# Main.net
KiCad netlist of a schematic drawn in Altium Designer
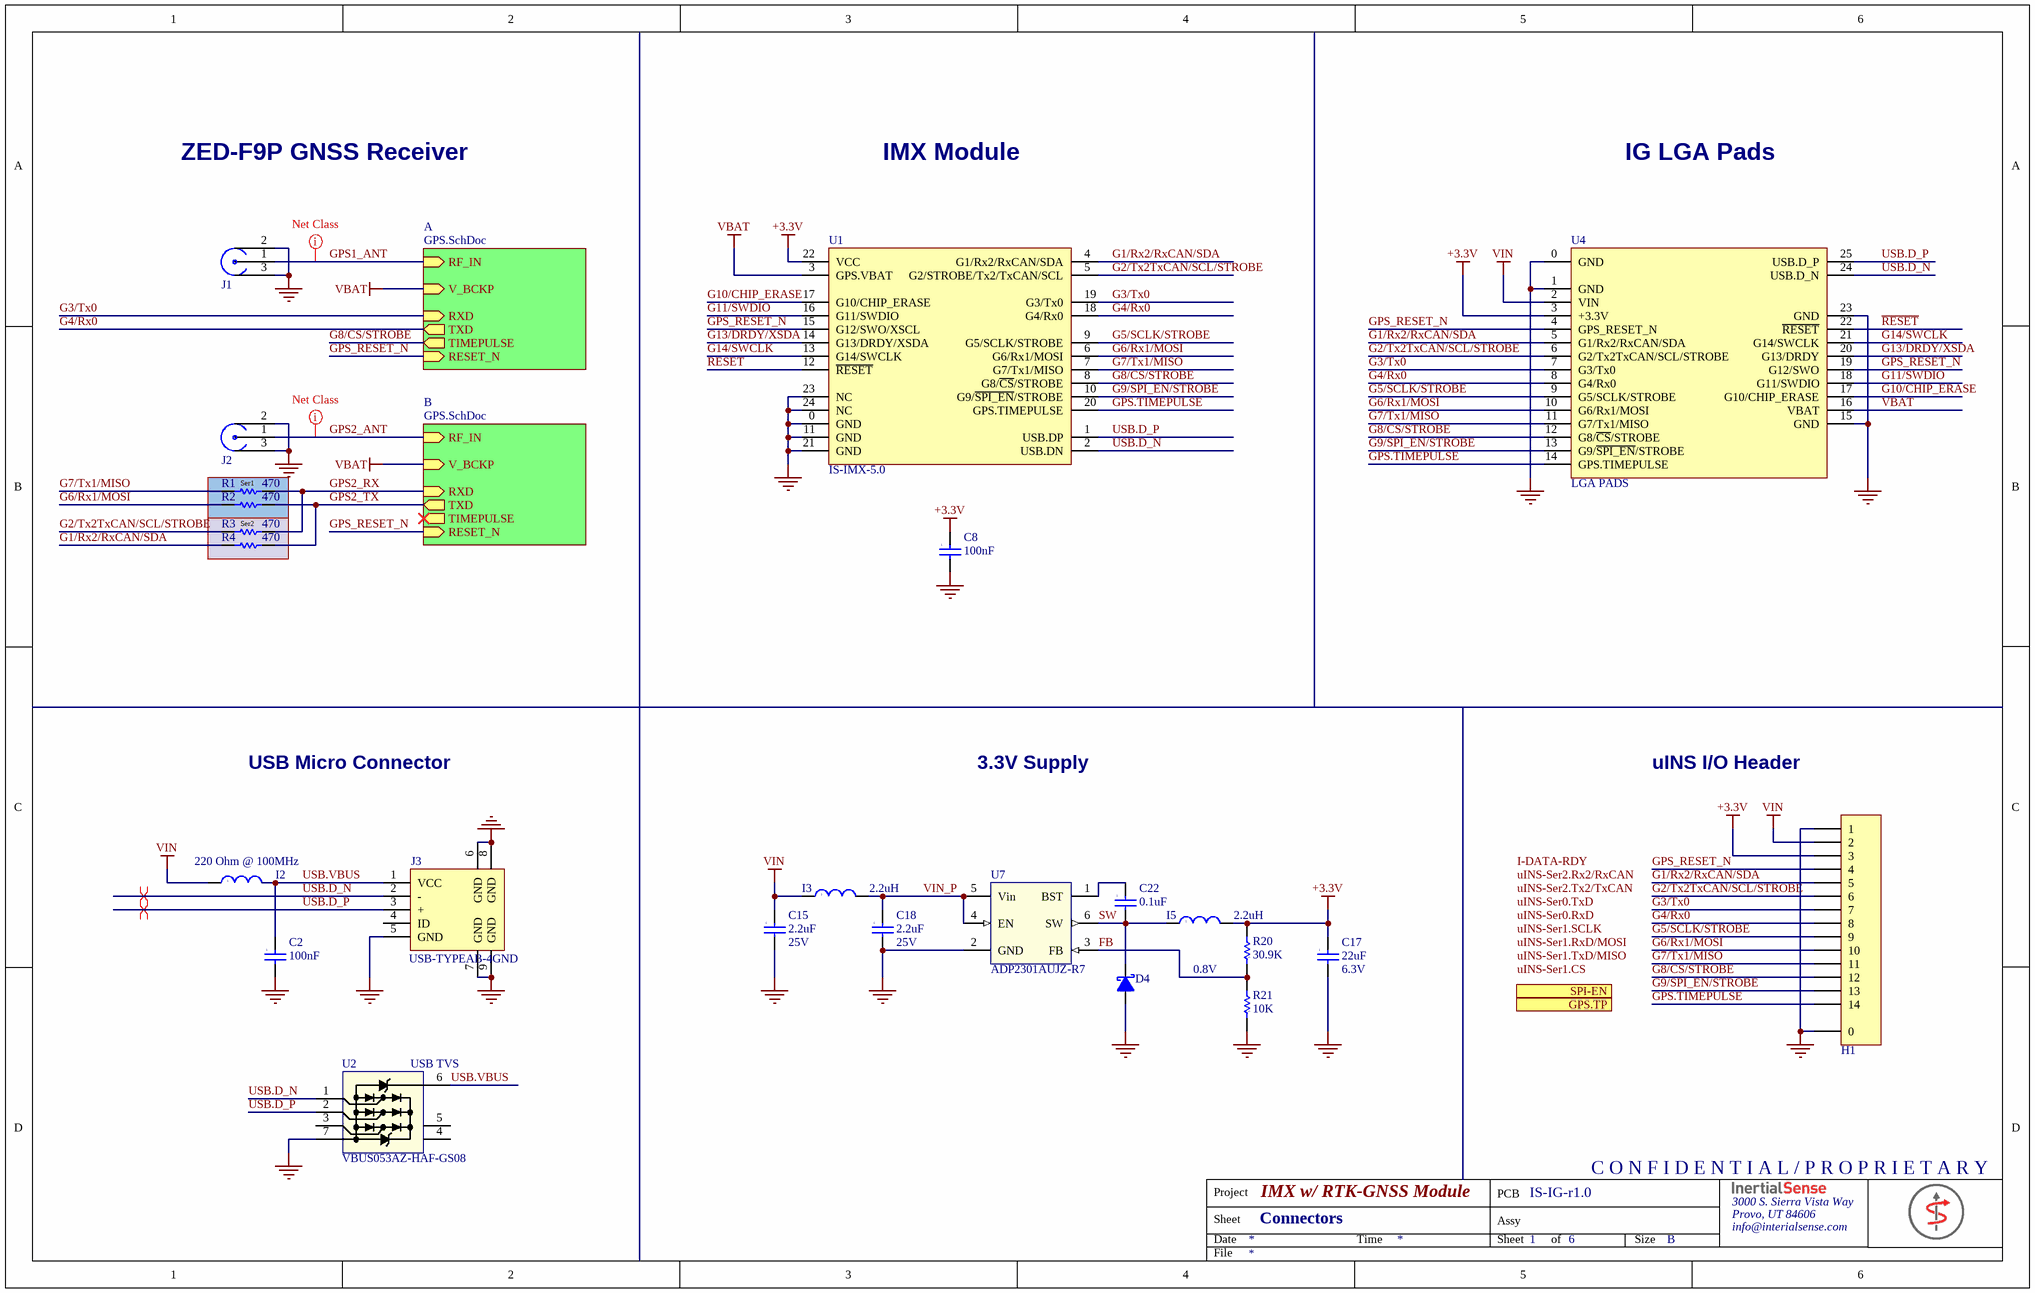
[diagram p0: Main.SchDoc]

(export (version "E")
  (design (tool "Eeschema 10.0.6"))
  (components
    (comp (ref "C2")
      (value "100nF")
      (footprint "0402")
      (description "CAP CER .10UF 50V X7R 10% 0402")
      (fields
        (field (name "MANUFACTURER") "TDK Corporation")
        (field (name "MANUFACTURER PART NUMBER") "C1005X7R1H104K")
        (field (name "PUBLISHER") "Altium Limited")
      )
      (libsource (lib "") (part "Cap_1"))
    )
    (comp (ref "C8")
      (value "100nF")
      (footprint "0402")
      (description "CAP CER .10UF 50V X7R 10% 0402")
      (fields
        (field (name "MANUFACTURER") "TDK Corporation")
        (field (name "MANUFACTURER PART NUMBER") "C1005X7R1H104K")
        (field (name "PUBLISHER") "Altium Limited")
      )
      (libsource (lib "") (part "Cap_1"))
    )
    (comp (ref "C15")
      (value "2.2uF")
      (footprint "0603")
      (description "CAP CER 2.2UF 25V X6S 0603")
      (fields
        (field (name "MANUFACTURER") "Murata")
        (field (name "MANUFACTURER PART NUMBER") "GRT188C81E225KE13D")
        (field (name "VOLTAGE RATING") "25V")
        (field (name "PUBLISHER") "Altium Limited")
      )
      (libsource (lib "General") (part "Cap"))
    )
    (comp (ref "C17")
      (value "22uF")
      (footprint "0603")
      (description "CAP CER 22UF 6.3V X6S 0603")
      (fields
        (field (name "MANUFACTURER") "Murata")
        (field (name "MANUFACTURER PART NUMBER") "GRM188C80J226ME15D")
        (field (name "VOLTAGE RATING") "6.3V")
        (field (name "PUBLISHER") "Altium Limited")
      )
      (libsource (lib "General") (part "Cap"))
    )
    (comp (ref "C18")
      (value "2.2uF")
      (footprint "0603")
      (description "CAP CER 2.2UF 25V X6S 0603")
      (fields
        (field (name "MANUFACTURER") "Murata")
        (field (name "MANUFACTURER PART NUMBER") "GRT188C81E225KE13D")
        (field (name "VOLTAGE RATING") "25V")
        (field (name "PUBLISHER") "Altium Limited")
      )
      (libsource (lib "General") (part "Cap"))
    )
    (comp (ref "C22")
      (value "0.1uF")
      (footprint "0402")
      (description "CAP CER 0.1UF 50V X7R 0402")
      (fields
        (field (name "MANUFACTURER") "TDK")
        (field (name "MANUFACTURER PART NUMBER") "CGA2B3X7R1H104K050BB")
        (field (name "PUBLISHER") "Altium Limited")
      )
      (libsource (lib "General") (part "Cap"))
    )
    (comp (ref "D4")
      (value "Diode - Schottky")
      (footprint "D0603B")
      (description "DIODE SCHOTTKY 30V 2A 0603")
      (fields
        (field (name "MANUFACTURER") "Vishay")
        (field (name "MANUFACTURER PART NUMBER") "VSKY20301608-G4-08")
      )
      (libsource (lib "General") (part "Diode - Schottky"))
    )
    (comp (ref "H1")
      (value "Hdr - 14pin - mount")
      (footprint "SM14B-GHS-TB(LF)(SN)")
      (description "Conn Shrouded Header HDR 14 POS 1.25mm Solder ST Top Entry SMD T/R")
      (fields
        (field (name "MANUFACTURER") "JST")
        (field (name "MANUFACTURER PART NUMBER") "SM14B-GHS-TB(LF)(SN)")
      )
      (libsource (lib "Connectors") (part "Hdr - 14pin - mount"))
    )
    (comp (ref "I2")
      (value "220 Ohm @ 100MHz")
      (footprint "I0603")
      (description "FERRITE CHIP 220 OHM 2500MA 0603")
      (fields
        (field (name "MANUFACTURER") "Murata Electronics North America")
        (field (name "MANUFACTURER PART NUMBER") "BLM18SG221TN1D")
      )
      (libsource (lib "") (part "Inductor_1"))
    )
    (comp (ref "I3")
      (value "2.2uH")
      (footprint "0806")
      (description "FIXED IND 2.2UH 1.2A 110 MOHM")
      (fields
        (field (name "MANUFACTURER") "TDK")
        (field (name "MANUFACTURER PART NUMBER") "MLP2016H2R2MT0S1")
      )
      (libsource (lib "General") (part "Inductor"))
    )
    (comp (ref "I5")
      (value "2.2uH")
      (footprint "0806")
      (description "FIXED IND 2.2UH 1.2A 110 MOHM")
      (fields
        (field (name "MANUFACTURER") "TDK")
        (field (name "MANUFACTURER PART NUMBER") "MLP2016H2R2MT0S1")
      )
      (libsource (lib "General") (part "Inductor"))
    )
    (comp (ref "J1")
      (value "RF - GND x 2")
      (footprint "RF UMC SMD")
      (description "CONN UMC RCPT STR 50 OHM SMD")
      (fields
        (field (name "MANUFACTURER") "Emerson Network Power Connectivity Johnson")
        (field (name "MANUFACTURER PART NUMBER") "128-0711-201")
      )
      (libsource (lib "Connectors") (part "RF - GND x 2"))
    )
    (comp (ref "J2")
      (value "RF - GND x 2")
      (footprint "RF UMC SMD")
      (description "CONN UMC RCPT STR 50 OHM SMD")
      (fields
        (field (name "MANUFACTURER") "Emerson Network Power Connectivity Johnson")
        (field (name "MANUFACTURER PART NUMBER") "128-0711-201")
      )
      (libsource (lib "Connectors") (part "RF - GND x 2"))
    )
    (comp (ref "J3")
      (value "USB-TYPEAB-4GND")
      (footprint "USB Micro AB R/A THR")
      (description "CONN USB AB 4POS")
      (fields
        (field (name "MANUFACTURER") "Amphenol FCI")
        (field (name "MANUFACTURER PART NUMBER") "10118194-0001LF")
      )
      (libsource (lib "Connectors") (part "USB-TYPEAB-4GND"))
    )
    (comp (ref "R1")
      (value "470")
      (footprint "R0402")
      (description "RES 470 OHM 1/16W 1% 0402 SMD")
      (fields
        (field (name "MANUFACTURER") "Vishay Dale")
        (field (name "MANUFACTURER PART NUMBER") "CRCW0402470RFKED")
      )
      (libsource (lib "") (part "Res_1"))
    )
    (comp (ref "R2")
      (value "470")
      (footprint "R0402")
      (description "RES 470 OHM 1/16W 1% 0402 SMD")
      (fields
        (field (name "MANUFACTURER") "Vishay Dale")
        (field (name "MANUFACTURER PART NUMBER") "CRCW0402470RFKED")
      )
      (libsource (lib "") (part "Res_1"))
    )
    (comp (ref "R3")
      (value "470")
      (footprint "R0402")
      (description "RES 470 OHM 1/16W 1% 0402 SMD")
      (fields
        (field (name "MANUFACTURER") "Vishay Dale")
        (field (name "MANUFACTURER PART NUMBER") "CRCW0402470RFKED")
      )
      (libsource (lib "") (part "Res_1"))
    )
    (comp (ref "R4")
      (value "470")
      (footprint "R0402")
      (description "RES 470 OHM 1/16W 1% 0402 SMD")
      (fields
        (field (name "MANUFACTURER") "Vishay Dale")
        (field (name "MANUFACTURER PART NUMBER") "CRCW0402470RFKED")
      )
      (libsource (lib "") (part "Res_1"))
    )
    (comp (ref "R20")
      (value "30.9K")
      (footprint "R0402")
      (description "RES TF 30.9K OHM 1% 1/16W 0402")
      (fields
        (field (name "MANUFACTURER") "Stackpole Electronics Inc")
        (field (name "MANUFACTURER PART NUMBER") "RMCF0402FT30K9")
      )
      (libsource (lib "General") (part "Res"))
    )
    (comp (ref "R21")
      (value "10K")
      (footprint "R0402")
      (description "RES 10.0K OHM 1/16W 1% 0402 SMD")
      (fields
        (field (name "MANUFACTURER") "Yageo")
        (field (name "MANUFACTURER PART NUMBER") "RC0402FR-0710KL")
      )
      (libsource (lib "General") (part "Res"))
    )
    (comp (ref "U1")
      (value "IMX")
      (footprint "IS-IMX-5.0")
      (description "Inertial Sense IMX")
      (fields
        (field (name "MANUFACTURER") "Inertial Sense")
        (field (name "MANUFACTURER PART NUMBER") "IS-IMX-5.0")
      )
      (libsource (lib "IS-IMX-5") (part "IS-IMX-5.0"))
    )
    (comp (ref "U2")
      (value "VBUS053")
      (footprint "QFN50P160X160X60-6N")
      (description "ESD SUPPRESS 5.5V 36W 3-Line USB")
      (fields
        (field (name "MANUFACTURER") "Vishay Semiconductors")
        (field (name "MANUFACTURER PART NUMBER") "VBUS053AZ-HAF-GS08")
      )
      (libsource (lib "ICs") (part "VBUS053"))
    )
    (comp (ref "U4")
      (value "LGA PADS")
      (footprint "IG-1.0_LGA")
      (description "IMX multi-frequency RTK-GNSS Module")
      (libsource (lib "Sensors") (part "IG_1.0_LGA"))
    )
    (comp (ref "U7")
      (value "ADP2301")
      (footprint "MO-178-AB")
      (description "IC BUCK ADJ 1.2A 6TSOT")
      (fields
        (field (name "MANUFACTURER") "Analog Devices Inc")
        (field (name "MANUFACTURER PART NUMBER") "ADP2301AUJZ-R7")
      )
      (libsource (lib "ICs") (part "ADP2301"))
    )
  )
  (nets
    (net (code "1") (name "+3.3V") (class "Default")
      (node (ref "C17") (pin "1") (pinfunction "1_1") (pintype "passive"))
      (node (ref "C8") (pin "1") (pinfunction "1_1") (pintype "passive"))
      (node (ref "H1") (pin "3") (pinfunction "3_3") (pintype "passive"))
      (node (ref "I5") (pin "2") (pinfunction "2_2") (pintype "passive"))
      (node (ref "R20") (pin "2") (pinfunction "2_2") (pintype "passive"))
      (node (ref "U1") (pin "22") (pinfunction "VCC_22") (pintype "power_in"))
      (node (ref "U4") (pin "3") (pinfunction "+3.3V_3") (pintype "passive"))
    )
    (net (code "2") (name "/FB") (class "Default")
      (node (ref "R20") (pin "1") (pinfunction "1_1") (pintype "passive"))
      (node (ref "R21") (pin "2") (pinfunction "2_2") (pintype "passive"))
      (node (ref "U7") (pin "3") (pinfunction "FB_3") (pintype "input"))
    )
    (net (code "3") (name "/G1{slash}Rx2{slash}RxCAN{slash}SDA") (class "Default")
      (node (ref "H1") (pin "5") (pinfunction "5_5") (pintype "passive"))
      (node (ref "R4") (pin "1") (pinfunction "1_1") (pintype "passive"))
      (node (ref "U1") (pin "4") (pinfunction "G1/Rx2/RxCAN/SDA_4") (pintype "passive"))
      (node (ref "U4") (pin "5") (pinfunction "G1/Rx2/RxCAN/SDA_5") (pintype "passive"))
    )
    (net (code "4") (name "/G2{slash}Tx2TxCAN{slash}SCL{slash}STROBE") (class "Default")
      (node (ref "H1") (pin "6") (pinfunction "6_6") (pintype "passive"))
      (node (ref "R3") (pin "1") (pinfunction "1_1") (pintype "passive"))
      (node (ref "U1") (pin "5") (pinfunction "G2/STROBE/Tx2/TxCAN/SCL_5") (pintype "passive"))
      (node (ref "U4") (pin "6") (pinfunction "G2/Tx2TxCAN/SCL/STROBE_6") (pintype "passive"))
    )
    (net (code "5") (name "/G3{slash}Tx0") (class "Default")
      (node (ref "H1") (pin "7") (pinfunction "7_7") (pintype "passive"))
      (node (ref "U1") (pin "19") (pinfunction "G3/Tx0_19") (pintype "passive"))
      (node (ref "U4") (pin "7") (pinfunction "G3/Tx0_7") (pintype "passive"))
    )
    (net (code "6") (name "/G4{slash}Rx0") (class "Default")
      (node (ref "H1") (pin "8") (pinfunction "8_8") (pintype "passive"))
      (node (ref "U1") (pin "18") (pinfunction "G4/Rx0_18") (pintype "passive"))
      (node (ref "U4") (pin "8") (pinfunction "G4/Rx0_8") (pintype "passive"))
    )
    (net (code "7") (name "/G5{slash}SCLK{slash}STROBE") (class "Default")
      (node (ref "H1") (pin "9") (pinfunction "9_9") (pintype "passive"))
      (node (ref "U1") (pin "9") (pinfunction "G5/SCLK/STROBE_9") (pintype "passive"))
      (node (ref "U4") (pin "9") (pinfunction "G5/SCLK/STROBE_9") (pintype "passive"))
    )
    (net (code "8") (name "/G6{slash}Rx1{slash}MOSI") (class "Default")
      (node (ref "H1") (pin "10") (pinfunction "10_10") (pintype "passive"))
      (node (ref "R2") (pin "1") (pinfunction "1_1") (pintype "passive"))
      (node (ref "U1") (pin "6") (pinfunction "G6/Rx1/MOSI_6") (pintype "passive"))
      (node (ref "U4") (pin "10") (pinfunction "G6/Rx1/MOSI_10") (pintype "passive"))
    )
    (net (code "9") (name "/G7{slash}Tx1{slash}MISO") (class "Default")
      (node (ref "H1") (pin "11") (pinfunction "11_11") (pintype "passive"))
      (node (ref "R1") (pin "1") (pinfunction "1_1") (pintype "passive"))
      (node (ref "U1") (pin "7") (pinfunction "G7/Tx1/MISO_7") (pintype "passive"))
      (node (ref "U4") (pin "11") (pinfunction "G7/Tx1/MISO_11") (pintype "passive"))
    )
    (net (code "10") (name "/G8{slash}~{CS}{slash}STROBE") (class "Default")
      (node (ref "H1") (pin "12") (pinfunction "12_12") (pintype "passive"))
      (node (ref "U1") (pin "8") (pinfunction "G8/~{CS}/STROBE_8") (pintype "passive"))
      (node (ref "U4") (pin "12") (pinfunction "G8/~{CS}/STROBE_12") (pintype "passive"))
    )
    (net (code "11") (name "/G9{slash}~{SPI_EN}{slash}STROBE") (class "Default")
      (node (ref "H1") (pin "13") (pinfunction "13_13") (pintype "passive"))
      (node (ref "U1") (pin "10") (pinfunction "G9/~{SPI_EN}/STROBE_10") (pintype "passive"))
      (node (ref "U4") (pin "13") (pinfunction "G9/~{SPI_EN}/STROBE_13") (pintype "passive"))
    )
    (net (code "12") (name "/G10{slash}CHIP_ERASE") (class "Default")
      (node (ref "U1") (pin "17") (pinfunction "G10/CHIP_ERASE_17") (pintype "passive"))
      (node (ref "U4") (pin "17") (pinfunction "G10/CHIP_ERASE_17") (pintype "passive"))
    )
    (net (code "13") (name "/G11{slash}SWDIO") (class "Default")
      (node (ref "U1") (pin "16") (pinfunction "G11/SWDIO_16") (pintype "passive"))
      (node (ref "U4") (pin "18") (pinfunction "G11/SWDIO_18") (pintype "passive"))
    )
    (net (code "14") (name "/G13{slash}DRDY{slash}XSDA") (class "Default")
      (node (ref "U1") (pin "14") (pinfunction "G13/DRDY/XSDA_14") (pintype "passive"))
      (node (ref "U4") (pin "20") (pinfunction "G13/DRDY_20") (pintype "passive"))
    )
    (net (code "15") (name "/G14{slash}SWCLK") (class "Default")
      (node (ref "U1") (pin "13") (pinfunction "G14/SWCLK_13") (pintype "passive"))
      (node (ref "U4") (pin "21") (pinfunction "G14/SWCLK_21") (pintype "passive"))
    )
    (net (code "16") (name "/GPS.TIMEPULSE") (class "Default")
      (node (ref "H1") (pin "14") (pinfunction "14_14") (pintype "passive"))
      (node (ref "U1") (pin "20") (pinfunction "GPS.TIMEPULSE_20") (pintype "passive"))
      (node (ref "U4") (pin "14") (pinfunction "GPS.TIMEPULSE_14") (pintype "passive"))
    )
    (net (code "18") (name "/GPS1_ANT") (class "Default")
      (node (ref "J1") (pin "1") (pinfunction "1_1") (pintype "passive"))
    )
    (net (code "19") (name "/GPS2_ANT") (class "Default")
      (node (ref "J2") (pin "1") (pinfunction "1_1") (pintype "passive"))
    )
    (net (code "20") (name "/GPS2_RX") (class "Default")
      (node (ref "R1") (pin "2") (pinfunction "2_2") (pintype "passive"))
      (node (ref "R3") (pin "2") (pinfunction "2_2") (pintype "passive"))
    )
    (net (code "21") (name "/GPS2_TX") (class "Default")
      (node (ref "R2") (pin "2") (pinfunction "2_2") (pintype "passive"))
      (node (ref "R4") (pin "2") (pinfunction "2_2") (pintype "passive"))
    )
    (net (code "22") (name "/GPS_RESET_N") (class "Default")
      (node (ref "H1") (pin "4") (pinfunction "4_4") (pintype "passive"))
      (node (ref "U1") (pin "15") (pinfunction "G12/SWO/XSCL_15") (pintype "passive"))
      (node (ref "U4") (pin "19") (pinfunction "G12/SWO_19") (pintype "passive"))
      (node (ref "U4") (pin "4") (pinfunction "GPS_RESET_N_4") (pintype "passive"))
    )
    (net (code "24") (name "/RESET") (class "Default")
      (node (ref "U1") (pin "12") (pinfunction "~{RESET}_12") (pintype "passive"))
      (node (ref "U4") (pin "22") (pinfunction "~{RESET}_22") (pintype "passive"))
    )
    (net (code "26") (name "/SW") (class "Default")
      (node (ref "C22") (pin "2") (pinfunction "2_2") (pintype "passive"))
      (node (ref "D4") (pin "C") (pinfunction "C_C") (pintype "passive"))
      (node (ref "I5") (pin "1") (pinfunction "1_1") (pintype "passive"))
      (node (ref "U7") (pin "6") (pinfunction "SW_6") (pintype "output"))
    )
    (net (code "28") (name "/USB.D_N") (class "Default")
      (node (ref "J3") (pin "2") (pinfunction "-_2") (pintype "passive"))
      (node (ref "U1") (pin "2") (pinfunction "USB.DN_2") (pintype "passive"))
      (node (ref "U2") (pin "1") (pintype "passive"))
      (node (ref "U4") (pin "24") (pinfunction "USB.D_N_24") (pintype "passive"))
    )
    (net (code "29") (name "/USB.D_P") (class "Default")
      (node (ref "J3") (pin "3") (pinfunction "+_3") (pintype "passive"))
      (node (ref "U1") (pin "1") (pinfunction "USB.DP_1") (pintype "passive"))
      (node (ref "U2") (pin "2") (pintype "passive"))
      (node (ref "U4") (pin "25") (pinfunction "USB.D_P_25") (pintype "passive"))
    )
    (net (code "30") (name "/USB.VBUS") (class "Default")
      (node (ref "C2") (pin "1") (pinfunction "1_1") (pintype "passive"))
      (node (ref "I2") (pin "2") (pinfunction "2_2") (pintype "passive"))
      (node (ref "J3") (pin "1") (pinfunction "VCC_1") (pintype "passive"))
      (node (ref "U2") (pin "6") (pintype "passive"))
    )
    (net (code "31") (name "/VIN_P") (class "Default")
      (node (ref "C18") (pin "1") (pinfunction "1_1") (pintype "passive"))
      (node (ref "I3") (pin "2") (pinfunction "2_2") (pintype "passive"))
      (node (ref "U7") (pin "4") (pinfunction "EN_4") (pintype "input"))
      (node (ref "U7") (pin "5") (pinfunction "Vin_5") (pintype "power_in"))
    )
    (net (code "40") (name "GND") (class "Default")
      (node (ref "C15") (pin "2") (pinfunction "2_2") (pintype "passive"))
      (node (ref "C17") (pin "2") (pinfunction "2_2") (pintype "passive"))
      (node (ref "C18") (pin "2") (pinfunction "2_2") (pintype "passive"))
      (node (ref "C2") (pin "2") (pinfunction "2_2") (pintype "passive"))
      (node (ref "C8") (pin "2") (pinfunction "2_2") (pintype "passive"))
      (node (ref "D4") (pin "A") (pinfunction "A_A") (pintype "passive"))
      (node (ref "H1") (pin "0") (pinfunction "0_0") (pintype "passive"))
      (node (ref "H1") (pin "1") (pinfunction "1_1") (pintype "passive"))
      (node (ref "J1") (pin "2") (pinfunction "2_2") (pintype "passive"))
      (node (ref "J1") (pin "3") (pinfunction "3_3") (pintype "passive"))
      (node (ref "J2") (pin "2") (pinfunction "2_2") (pintype "passive"))
      (node (ref "J2") (pin "3") (pinfunction "3_3") (pintype "passive"))
      (node (ref "J3") (pin "5") (pinfunction "GND_5") (pintype "passive"))
      (node (ref "J3") (pin "6") (pinfunction "GND_6") (pintype "passive"))
      (node (ref "J3") (pin "7") (pinfunction "GND_7") (pintype "passive"))
      (node (ref "J3") (pin "8") (pinfunction "GND_8") (pintype "passive"))
      (node (ref "J3") (pin "9") (pinfunction "GND_9") (pintype "passive"))
      (node (ref "R21") (pin "1") (pinfunction "1_1") (pintype "passive"))
      (node (ref "U1") (pin "0") (pinfunction "GND_0") (pintype "power_in"))
      (node (ref "U1") (pin "11") (pinfunction "GND_11") (pintype "power_in"))
      (node (ref "U1") (pin "21") (pinfunction "GND_21") (pintype "power_in"))
      (node (ref "U1") (pin "23") (pinfunction "NC_23") (pintype "power_in"))
      (node (ref "U1") (pin "24") (pinfunction "NC_24") (pintype "power_in"))
      (node (ref "U2") (pin "7") (pintype "passive"))
      (node (ref "U4") (pin "0") (pinfunction "GND_0") (pintype "passive"))
      (node (ref "U4") (pin "1") (pinfunction "GND_1") (pintype "passive"))
      (node (ref "U4") (pin "15") (pinfunction "GND_15") (pintype "passive"))
      (node (ref "U4") (pin "23") (pinfunction "GND_23") (pintype "passive"))
      (node (ref "U7") (pin "2") (pinfunction "GND_2") (pintype "power_in"))
    )
    (net (code "41") (name "Net-(U7-BST)") (class "Default")
      (node (ref "C22") (pin "1") (pinfunction "1_1") (pintype "passive"))
      (node (ref "U7") (pin "1") (pinfunction "BST_1") (pintype "passive"))
    )
    (net (code "42") (name "VBAT") (class "Default")
      (node (ref "U1") (pin "3") (pinfunction "GPS.VBAT_3") (pintype "passive"))
      (node (ref "U4") (pin "16") (pinfunction "VBAT_16") (pintype "passive"))
    )
    (net (code "43") (name "VIN") (class "Default")
      (node (ref "C15") (pin "1") (pinfunction "1_1") (pintype "passive"))
      (node (ref "H1") (pin "2") (pinfunction "2_2") (pintype "passive"))
      (node (ref "I2") (pin "1") (pinfunction "1_1") (pintype "passive"))
      (node (ref "I3") (pin "1") (pinfunction "1_1") (pintype "passive"))
      (node (ref "U4") (pin "2") (pinfunction "VIN_2") (pintype "passive"))
    )
    (net (code "44") (name "unconnected-(J3-ID-Pad4)") (class "Default")
      (node (ref "J3") (pin "4") (pinfunction "ID_4") (pintype "passive"))
    )
    (net (code "45") (name "unconnected-(U2-Pad3)") (class "Default")
      (node (ref "U2") (pin "3") (pintype "passive"))
    )
    (net (code "46") (name "unconnected-(U2-nc-Pad4)") (class "Default")
      (node (ref "U2") (pin "4") (pinfunction "nc_4") (pintype "passive"))
    )
    (net (code "47") (name "unconnected-(U2-nc-Pad5)") (class "Default")
      (node (ref "U2") (pin "5") (pinfunction "nc_5") (pintype "passive"))
    )
  )
)
